# SHC_TB6612FNG.net
KiCad netlist of a schematic drawn in Altium Designer
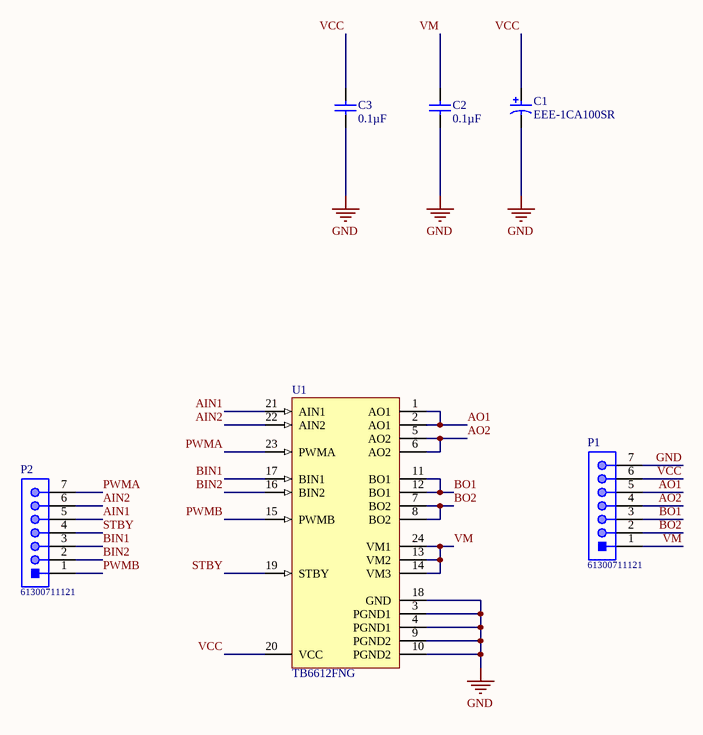
[diagram p0: SHC_TB6612FNG.SchDoc]

(export (version "E")
  (design (tool "Eeschema 10.0.6"))
  (components
    (comp (ref "C1")
      (value "EEE-1CA100SR")
      (footprint "PNSC-EEE1CA100SR_M")
      (description "Aluminum Electrolytic Capacitor, 10 uF, +/- 20%, -40 to 85 degC, 2-Pin SMD, RoHS, Tape and Reel")
      (fields (field (name "MANUFACTURER") "Panasonic"))
      (libsource (lib "Altium Content Vault") (part "CAP-P-2"))
    )
    (comp (ref "C2")
      (value "0.1µF")
      (footprint "CAPC2013X140X50ML20T25")
      (description "10µF ±10% 16V Ceramic Capacitor X5R 0805 (2012 Metric)")
      (fields (field (name "PART NUMBER") "CL21A106KOQNNNG"))
      (libsource (lib "Altium Content Vault") (part "CAP"))
    )
    (comp (ref "C3")
      (value "0.1µF")
      (footprint "CAPC2013X140X50ML20T25")
      (description "10µF ±10% 16V Ceramic Capacitor X5R 0805 (2012 Metric)")
      (fields (field (name "PART NUMBER") "CL21A106KOQNNNG"))
      (libsource (lib "Altium Content Vault") (part "CAP"))
    )
    (comp (ref "P1")
      (value "61300711121")
      (footprint "61300711121")
      (description "THT Vertical Pin Header WR-PHD, Pitch 2.54 mm, Single Row, 7 pins")
      (fields (field (name "MANUFACTURER") "Wurth Elektronik") (field (name "PUBLISHER") "WurthElektronik"))
      (libsource (lib "Altium Content Vault") (part "WE-CN-1P-M-R7"))
    )
    (comp (ref "P2")
      (value "61300711121")
      (footprint "61300711121")
      (description "THT Vertical Pin Header WR-PHD, Pitch 2.54 mm, Single Row, 7 pins")
      (fields (field (name "MANUFACTURER") "Wurth Elektronik") (field (name "PUBLISHER") "WurthElektronik"))
      (libsource (lib "Altium Content Vault") (part "WE-CN-1P-M-R7"))
    )
    (comp (ref "U1")
      (value "TB6612FNG")
      (footprint "TOSH-SSOP-24_M")
      (description "Driver IC for Dual DC Motor, 15 V, -20 to 85 degC, 24-Pin SSOP, RoHS, Tape and Reel")
      (libsource (lib "Altium Content Vault") (part "TOSH-TB6612FNG-SOP-24"))
    )
  )
  (nets
    (net (code "1") (name "/AIN1") (class "Default")
      (node (ref "P2") (pin "5") (pinfunction "5_5") (pintype "passive"))
      (node (ref "U1") (pin "21") (pinfunction "AIN1_21") (pintype "input"))
    )
    (net (code "2") (name "/AIN2") (class "Default")
      (node (ref "P2") (pin "6") (pinfunction "6_6") (pintype "passive"))
      (node (ref "U1") (pin "22") (pinfunction "AIN2_22") (pintype "input"))
    )
    (net (code "3") (name "/AO1") (class "Default")
      (node (ref "P1") (pin "5") (pinfunction "5_5") (pintype "passive"))
      (node (ref "U1") (pin "1") (pinfunction "AO1_1") (pintype "tri_state"))
      (node (ref "U1") (pin "2") (pinfunction "AO1_2") (pintype "tri_state"))
    )
    (net (code "4") (name "/AO2") (class "Default")
      (node (ref "P1") (pin "4") (pinfunction "4_4") (pintype "passive"))
      (node (ref "U1") (pin "5") (pinfunction "AO2_5") (pintype "tri_state"))
      (node (ref "U1") (pin "6") (pinfunction "AO2_6") (pintype "tri_state"))
    )
    (net (code "5") (name "/BIN1") (class "Default")
      (node (ref "P2") (pin "3") (pinfunction "3_3") (pintype "passive"))
      (node (ref "U1") (pin "17") (pinfunction "BIN1_17") (pintype "input"))
    )
    (net (code "6") (name "/BIN2") (class "Default")
      (node (ref "P2") (pin "2") (pinfunction "2_2") (pintype "passive"))
      (node (ref "U1") (pin "16") (pinfunction "BIN2_16") (pintype "input"))
    )
    (net (code "7") (name "/BO1") (class "Default")
      (node (ref "P1") (pin "3") (pinfunction "3_3") (pintype "passive"))
      (node (ref "U1") (pin "11") (pinfunction "BO1_11") (pintype "tri_state"))
      (node (ref "U1") (pin "12") (pinfunction "BO1_12") (pintype "tri_state"))
    )
    (net (code "8") (name "/BO2") (class "Default")
      (node (ref "P1") (pin "2") (pinfunction "2_2") (pintype "passive"))
      (node (ref "U1") (pin "7") (pinfunction "BO2_7") (pintype "tri_state"))
      (node (ref "U1") (pin "8") (pinfunction "BO2_8") (pintype "tri_state"))
    )
    (net (code "9") (name "/PWMA") (class "Default")
      (node (ref "P2") (pin "7") (pinfunction "7_7") (pintype "passive"))
      (node (ref "U1") (pin "23") (pinfunction "PWMA_23") (pintype "input"))
    )
    (net (code "10") (name "/PWMB") (class "Default")
      (node (ref "P2") (pin "1") (pinfunction "1_1") (pintype "passive"))
      (node (ref "U1") (pin "15") (pinfunction "PWMB_15") (pintype "input"))
    )
    (net (code "11") (name "/STBY") (class "Default")
      (node (ref "P2") (pin "4") (pinfunction "4_4") (pintype "passive"))
      (node (ref "U1") (pin "19") (pinfunction "STBY_19") (pintype "input"))
    )
    (net (code "12") (name "/VCC") (class "Default")
      (node (ref "C1") (pin "1") (pinfunction "1_1") (pintype "passive"))
      (node (ref "C3") (pin "2") (pinfunction "2_2") (pintype "passive"))
      (node (ref "P1") (pin "6") (pinfunction "6_6") (pintype "passive"))
      (node (ref "U1") (pin "20") (pinfunction "VCC_20") (pintype "power_in"))
    )
    (net (code "13") (name "/VM") (class "Default")
      (node (ref "C2") (pin "2") (pinfunction "2_2") (pintype "passive"))
      (node (ref "P1") (pin "1") (pinfunction "1_1") (pintype "passive"))
      (node (ref "U1") (pin "13") (pinfunction "VM2_13") (pintype "power_in"))
      (node (ref "U1") (pin "14") (pinfunction "VM3_14") (pintype "power_in"))
      (node (ref "U1") (pin "24") (pinfunction "VM1_24") (pintype "power_in"))
    )
    (net (code "14") (name "GND") (class "Default")
      (node (ref "C1") (pin "2") (pinfunction "2_2") (pintype "passive"))
      (node (ref "C2") (pin "1") (pinfunction "1_1") (pintype "passive"))
      (node (ref "C3") (pin "1") (pinfunction "1_1") (pintype "passive"))
      (node (ref "P1") (pin "7") (pinfunction "7_7") (pintype "passive"))
      (node (ref "U1") (pin "10") (pinfunction "PGND2_10") (pintype "power_in"))
      (node (ref "U1") (pin "18") (pinfunction "GND_18") (pintype "power_in"))
      (node (ref "U1") (pin "3") (pinfunction "PGND1_3") (pintype "power_in"))
      (node (ref "U1") (pin "4") (pinfunction "PGND1_4") (pintype "power_in"))
      (node (ref "U1") (pin "9") (pinfunction "PGND2_9") (pintype "power_in"))
    )
  )
)
